# AU0001A.net
KiCad netlist of a schematic drawn in Altium Designer
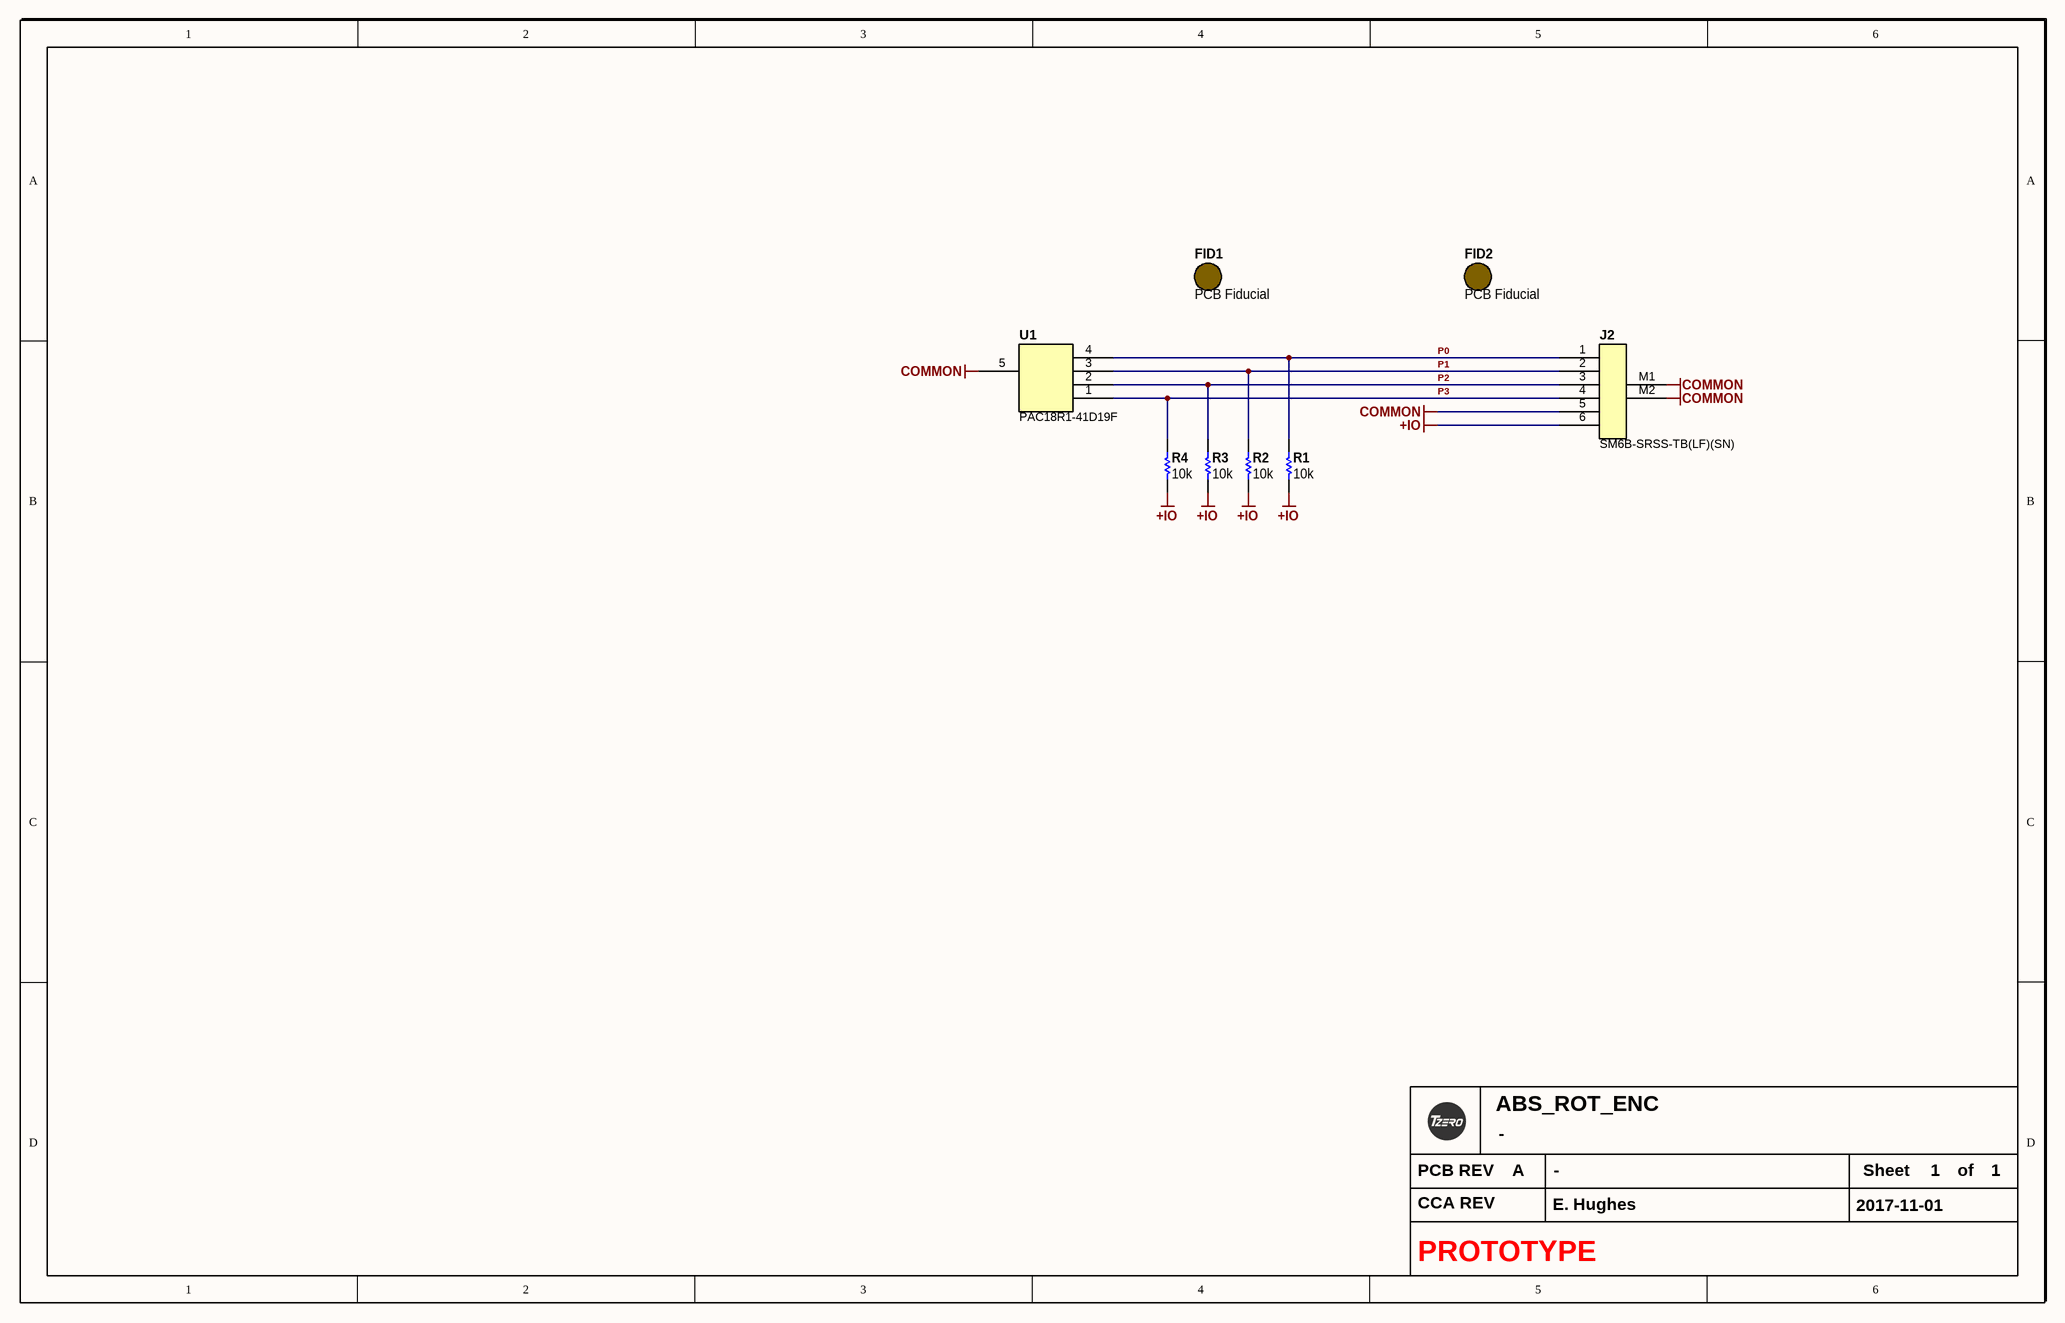
[diagram p0: AU0001A.SchDoc]

(export (version "E")
  (design (tool "Eeschema 10.0.6"))
  (components
    (comp (ref "FID1")
      (value "PCB Fiducial")
      (footprint "Fiducial 1mm - 2mm")
      (libsource (lib "eFiducial") (part "Fiducial"))
    )
    (comp (ref "FID2")
      (value "PCB Fiducial")
      (footprint "Fiducial 1mm - 2mm")
      (libsource (lib "eFiducial") (part "Fiducial"))
    )
    (comp (ref "J2")
      (value "SM6B-SRSS-TB(LF)(SN)")
      (footprint "SM06B-SRSS-TB(LF)(SN)")
      (description "6 Positions Header, Shrouded Connector 0.039\" (1.00mm) Surface Mount, Right Angle Tin")
      (fields
        (field (name "MANUFACTURER") "JST")
        (field (name "MANUFACTURER PART NUMBER") "SM06B-SRSS-TB(LF)(SN)")
      )
      (libsource (lib "eConnector_JST_SM") (part "SM06B-SRSS-TB(LF)(SN)"))
    )
    (comp (ref "R1")
      (value "10k")
      (footprint "R0603_0.55MM_MD")
      (description "RES 10K OHM 1/10W 1% 0603 SMD")
      (fields
        (field (name "MANUFACTURER PART NUMBER") "ERJ-3EKF1002V")
        (field (name "MANUFACTURER") "Panasonic Electronic Components")
      )
      (libsource (lib "Resistors - Panasonic - AEC-Q200") (part "R_2P"))
    )
    (comp (ref "R2")
      (value "10k")
      (footprint "R0603_0.55MM_MD")
      (description "RES 10K OHM 1/10W 1% 0603 SMD")
      (fields
        (field (name "MANUFACTURER PART NUMBER") "ERJ-3EKF1002V")
        (field (name "MANUFACTURER") "Panasonic Electronic Components")
      )
      (libsource (lib "Resistors - Panasonic - AEC-Q200") (part "R_2P"))
    )
    (comp (ref "R3")
      (value "10k")
      (footprint "R0603_0.55MM_MD")
      (description "RES 10K OHM 1/10W 1% 0603 SMD")
      (fields
        (field (name "MANUFACTURER PART NUMBER") "ERJ-3EKF1002V")
        (field (name "MANUFACTURER") "Panasonic Electronic Components")
      )
      (libsource (lib "Resistors - Panasonic - AEC-Q200") (part "R_2P"))
    )
    (comp (ref "R4")
      (value "10k")
      (footprint "R0603_0.55MM_MD")
      (description "RES 10K OHM 1/10W 1% 0603 SMD")
      (fields
        (field (name "MANUFACTURER PART NUMBER") "ERJ-3EKF1002V")
        (field (name "MANUFACTURER") "Panasonic Electronic Components")
      )
      (libsource (lib "Resistors - Panasonic - AEC-Q200") (part "R_2P"))
    )
    (comp (ref "U1")
      (value "PAC18R1-41D19F")
      (footprint "PAC18R1")
      (fields (field (name "MANUFACTURER") "Bourns"))
      (libsource (lib "eElectroMechanical") (part "PAC18R1-41D19F"))
    )
  )
  (nets
    (net (code "1") (name "+IO") (class "Default")
      (node (ref "J2") (pin "6") (pinfunction "6_6") (pintype "passive"))
      (node (ref "R1") (pin "1") (pinfunction "1_1") (pintype "passive"))
      (node (ref "R2") (pin "1") (pinfunction "1_1") (pintype "passive"))
      (node (ref "R3") (pin "1") (pinfunction "1_1") (pintype "passive"))
      (node (ref "R4") (pin "1") (pinfunction "1_1") (pintype "passive"))
    )
    (net (code "2") (name "/P0") (class "Default")
      (node (ref "J2") (pin "1") (pinfunction "1_1") (pintype "passive"))
      (node (ref "R1") (pin "2") (pinfunction "2_2") (pintype "passive"))
      (node (ref "U1") (pin "4") (pinfunction "4_4") (pintype "passive"))
    )
    (net (code "3") (name "/P1") (class "Default")
      (node (ref "J2") (pin "2") (pinfunction "2_2") (pintype "passive"))
      (node (ref "R2") (pin "2") (pinfunction "2_2") (pintype "passive"))
      (node (ref "U1") (pin "3") (pinfunction "3_3") (pintype "passive"))
    )
    (net (code "4") (name "/P2") (class "Default")
      (node (ref "J2") (pin "3") (pinfunction "3_3") (pintype "passive"))
      (node (ref "R3") (pin "2") (pinfunction "2_2") (pintype "passive"))
      (node (ref "U1") (pin "2") (pinfunction "2_2") (pintype "passive"))
    )
    (net (code "5") (name "/P3") (class "Default")
      (node (ref "J2") (pin "4") (pinfunction "4_4") (pintype "passive"))
      (node (ref "R4") (pin "2") (pinfunction "2_2") (pintype "passive"))
      (node (ref "U1") (pin "1") (pinfunction "1_1") (pintype "passive"))
    )
    (net (code "6") (name "COMMON") (class "Default")
      (node (ref "J2") (pin "5") (pinfunction "5_5") (pintype "passive"))
      (node (ref "J2") (pin "M1") (pinfunction "M1_M1") (pintype "passive"))
      (node (ref "J2") (pin "M2") (pinfunction "M2_M2") (pintype "passive"))
      (node (ref "U1") (pin "5") (pinfunction "5_5") (pintype "passive"))
    )
  )
)
